# Penetrometer_V3_PCB.net
KiCad netlist of a schematic drawn in EAGLE
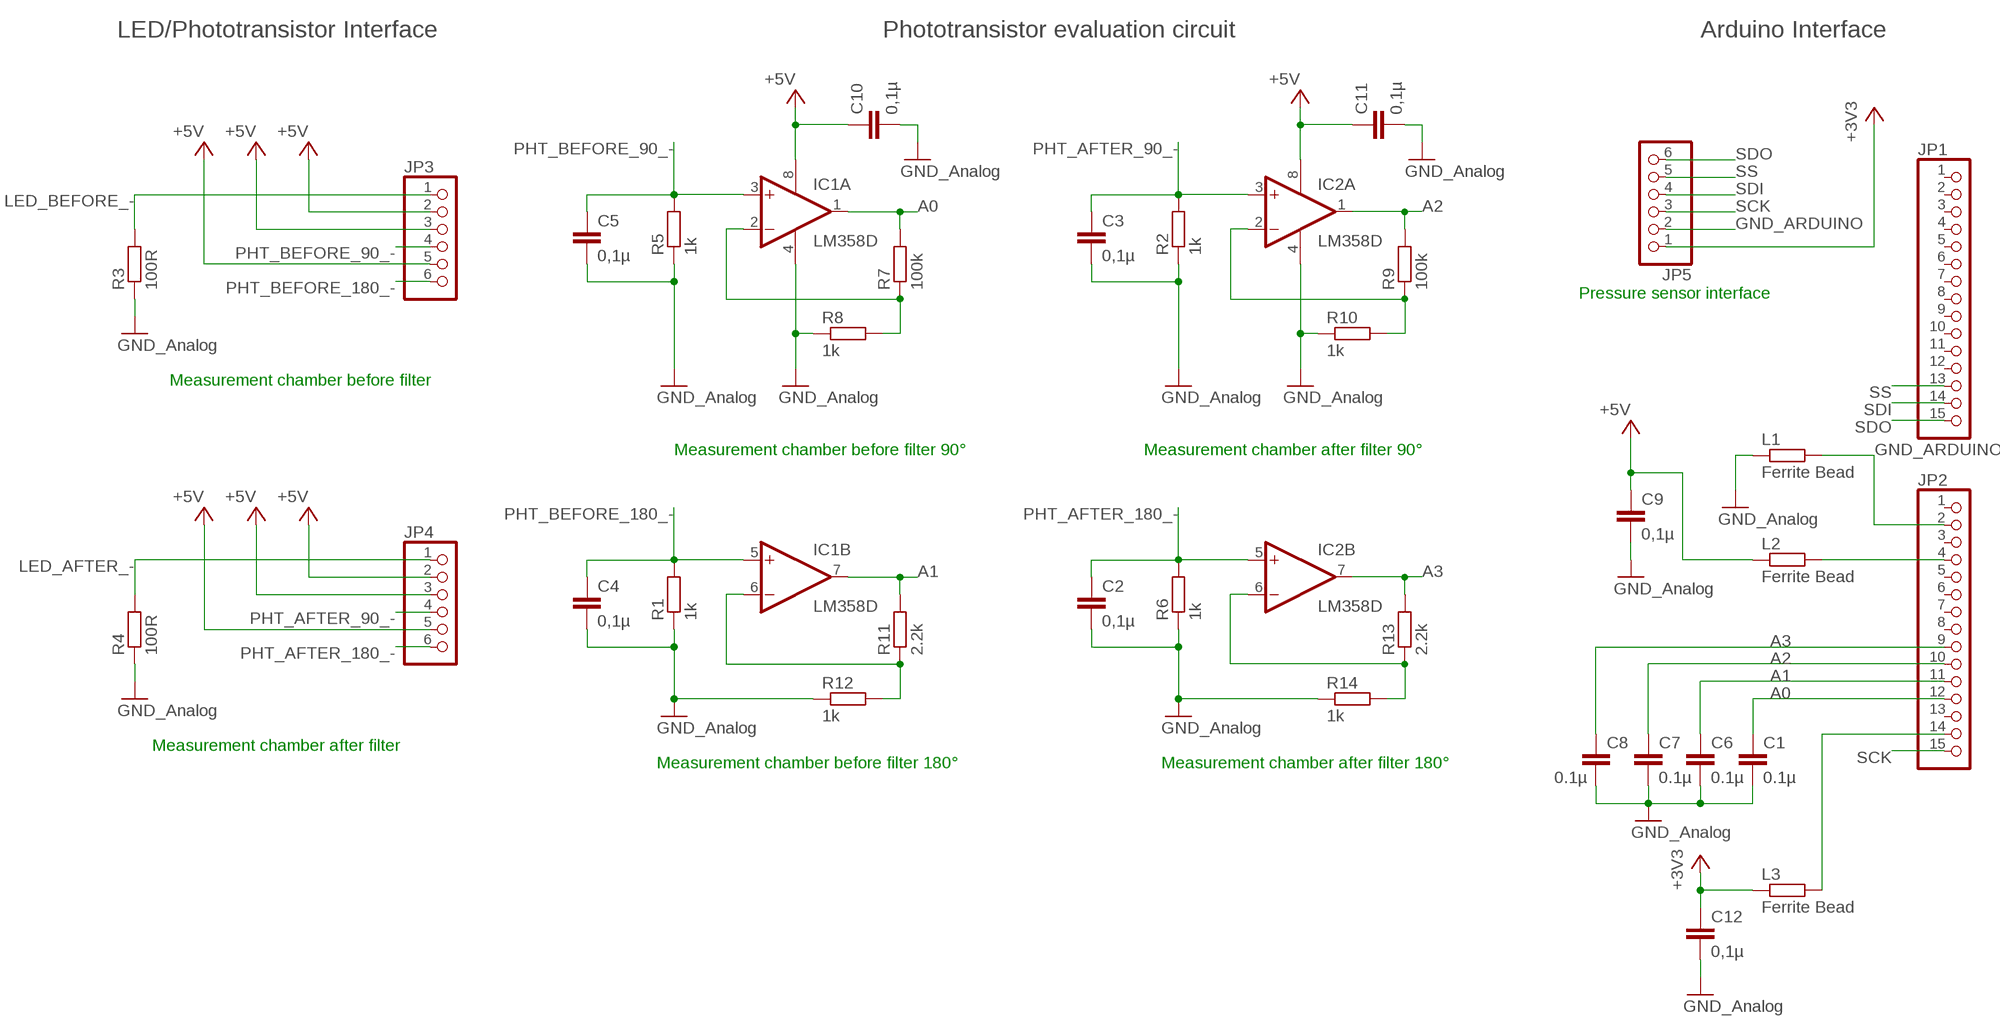
[diagram p0: schematic, sheet 1]

(export (version "E")
  (design (tool "Eeschema 10.0.6"))
  (components
    (comp (ref "C1")
      (value "0.1µ")
      (footprint "eagle-import:C0603K")
      (libsource (lib "eagle-import") (part "C-EUC0603K"))
    )
    (comp (ref "C2")
      (value "0,1µ")
      (footprint "eagle-import:C0603K")
      (libsource (lib "eagle-import") (part "C-EUC0603K"))
    )
    (comp (ref "C3")
      (value "0,1µ")
      (footprint "eagle-import:C0603K")
      (libsource (lib "eagle-import") (part "C-EUC0603K"))
    )
    (comp (ref "C4")
      (value "0,1µ")
      (footprint "eagle-import:C0603K")
      (libsource (lib "eagle-import") (part "C-EUC0603K"))
    )
    (comp (ref "C5")
      (value "0,1µ")
      (footprint "eagle-import:C0603K")
      (libsource (lib "eagle-import") (part "C-EUC0603K"))
    )
    (comp (ref "C6")
      (value "0.1µ")
      (footprint "eagle-import:C0603K")
      (libsource (lib "eagle-import") (part "C-EUC0603K"))
    )
    (comp (ref "C7")
      (value "0.1µ")
      (footprint "eagle-import:C0603K")
      (libsource (lib "eagle-import") (part "C-EUC0603K"))
    )
    (comp (ref "C8")
      (value "0.1µ")
      (footprint "eagle-import:C0603K")
      (libsource (lib "eagle-import") (part "C-EUC0603K"))
    )
    (comp (ref "C9")
      (value "0,1µ")
      (footprint "eagle-import:C0603K")
      (libsource (lib "eagle-import") (part "C-EUC0603K"))
    )
    (comp (ref "C10")
      (value "0,1µ")
      (footprint "eagle-import:C0603K")
      (libsource (lib "eagle-import") (part "C-EUC0603K"))
    )
    (comp (ref "C11")
      (value "0,1µ")
      (footprint "eagle-import:C0603K")
      (libsource (lib "eagle-import") (part "C-EUC0603K"))
    )
    (comp (ref "C12")
      (value "0,1µ")
      (footprint "eagle-import:C0603K")
      (libsource (lib "eagle-import") (part "C-EUC0603K"))
    )
    (comp (ref "IC1")
      (value "LM358D")
      (footprint "eagle-import:SO08")
      (libsource (lib "eagle-import") (part "LM358D"))
    )
    (comp (ref "IC2")
      (value "LM358D")
      (footprint "eagle-import:SO08")
      (libsource (lib "eagle-import") (part "LM358D"))
    )
    (comp (ref "JP1")
      (value "PINHD-1X15")
      (footprint "eagle-import:1X15")
      (libsource (lib "eagle-import") (part "PINHD-1X15"))
    )
    (comp (ref "JP2")
      (value "PINHD-1X15")
      (footprint "eagle-import:1X15")
      (libsource (lib "eagle-import") (part "PINHD-1X15"))
    )
    (comp (ref "JP3")
      (value "PINHD-1X6")
      (footprint "eagle-import:1X06")
      (libsource (lib "eagle-import") (part "PINHD-1X6"))
    )
    (comp (ref "JP4")
      (value "PINHD-1X6")
      (footprint "eagle-import:1X06")
      (libsource (lib "eagle-import") (part "PINHD-1X6"))
    )
    (comp (ref "JP5")
      (value "PINHD-1X6")
      (footprint "eagle-import:1X06")
      (libsource (lib "eagle-import") (part "PINHD-1X6"))
    )
    (comp (ref "L1")
      (value "Ferrite Bead")
      (footprint "eagle-import:R0603")
      (libsource (lib "eagle-import") (part "R-EU_R0603"))
    )
    (comp (ref "L2")
      (value "Ferrite Bead")
      (footprint "eagle-import:R0603")
      (libsource (lib "eagle-import") (part "R-EU_R0603"))
    )
    (comp (ref "L3")
      (value "Ferrite Bead")
      (footprint "eagle-import:R0603")
      (libsource (lib "eagle-import") (part "R-EU_R0603"))
    )
    (comp (ref "R1")
      (value "1k")
      (footprint "eagle-import:R0603")
      (libsource (lib "eagle-import") (part "R-EU_R0603"))
    )
    (comp (ref "R2")
      (value "1k")
      (footprint "eagle-import:R0603")
      (libsource (lib "eagle-import") (part "R-EU_R0603"))
    )
    (comp (ref "R3")
      (value "100R")
      (footprint "eagle-import:R0603")
      (libsource (lib "eagle-import") (part "R-EU_R0603"))
    )
    (comp (ref "R4")
      (value "100R")
      (footprint "eagle-import:R0603")
      (libsource (lib "eagle-import") (part "R-EU_R0603"))
    )
    (comp (ref "R5")
      (value "1k")
      (footprint "eagle-import:R0603")
      (libsource (lib "eagle-import") (part "R-EU_R0603"))
    )
    (comp (ref "R6")
      (value "1k")
      (footprint "eagle-import:R0603")
      (libsource (lib "eagle-import") (part "R-EU_R0603"))
    )
    (comp (ref "R7")
      (value "100k")
      (footprint "eagle-import:R0603")
      (libsource (lib "eagle-import") (part "R-EU_R0603"))
    )
    (comp (ref "R8")
      (value "1k")
      (footprint "eagle-import:R0603")
      (libsource (lib "eagle-import") (part "R-EU_R0603"))
    )
    (comp (ref "R9")
      (value "100k")
      (footprint "eagle-import:R0603")
      (libsource (lib "eagle-import") (part "R-EU_R0603"))
    )
    (comp (ref "R10")
      (value "1k")
      (footprint "eagle-import:R0603")
      (libsource (lib "eagle-import") (part "R-EU_R0603"))
    )
    (comp (ref "R11")
      (value "2.2k")
      (footprint "eagle-import:R0603")
      (libsource (lib "eagle-import") (part "R-EU_R0603"))
    )
    (comp (ref "R12")
      (value "1k")
      (footprint "eagle-import:R0603")
      (libsource (lib "eagle-import") (part "R-EU_R0603"))
    )
    (comp (ref "R13")
      (value "2.2k")
      (footprint "eagle-import:R0603")
      (libsource (lib "eagle-import") (part "R-EU_R0603"))
    )
    (comp (ref "R14")
      (value "1k")
      (footprint "eagle-import:R0603")
      (libsource (lib "eagle-import") (part "R-EU_R0603"))
    )
  )
  (nets
    (net (code "1") (name "+3V3") (class "Default")
      (node (ref "C12") (pin "1") (pinfunction "1_1") (pintype "passive"))
      (node (ref "JP5") (pin "1") (pinfunction "1_1") (pintype "passive"))
      (node (ref "L3") (pin "1") (pinfunction "1_1") (pintype "passive"))
    )
    (net (code "2") (name "+5V") (class "Default")
      (node (ref "C10") (pin "1") (pinfunction "1_1") (pintype "passive"))
      (node (ref "C11") (pin "1") (pinfunction "1_1") (pintype "passive"))
      (node (ref "C9") (pin "1") (pinfunction "1_1") (pintype "passive"))
      (node (ref "IC1") (pin "8") (pinfunction "V+_8") (pintype "power_in"))
      (node (ref "IC2") (pin "8") (pinfunction "V+_8") (pintype "power_in"))
      (node (ref "JP3") (pin "2") (pinfunction "2_2") (pintype "passive"))
      (node (ref "JP3") (pin "3") (pinfunction "3_3") (pintype "passive"))
      (node (ref "JP3") (pin "5") (pinfunction "5_5") (pintype "passive"))
      (node (ref "JP4") (pin "2") (pinfunction "2_2") (pintype "passive"))
      (node (ref "JP4") (pin "3") (pinfunction "3_3") (pintype "passive"))
      (node (ref "JP4") (pin "5") (pinfunction "5_5") (pintype "passive"))
      (node (ref "L2") (pin "1") (pinfunction "1_1") (pintype "passive"))
    )
    (net (code "3") (name "/A0") (class "Default")
      (node (ref "C1") (pin "1") (pinfunction "1_1") (pintype "passive"))
      (node (ref "IC1") (pin "1") (pinfunction "OUT_1") (pintype "output"))
      (node (ref "JP2") (pin "12") (pinfunction "12_12") (pintype "passive"))
      (node (ref "R7") (pin "2") (pinfunction "2_2") (pintype "passive"))
    )
    (net (code "4") (name "/A1") (class "Default")
      (node (ref "C6") (pin "1") (pinfunction "1_1") (pintype "passive"))
      (node (ref "IC1") (pin "7") (pinfunction "OUT_7") (pintype "output"))
      (node (ref "JP2") (pin "11") (pinfunction "11_11") (pintype "passive"))
      (node (ref "R11") (pin "2") (pinfunction "2_2") (pintype "passive"))
    )
    (net (code "5") (name "/A2") (class "Default")
      (node (ref "C7") (pin "1") (pinfunction "1_1") (pintype "passive"))
      (node (ref "IC2") (pin "1") (pinfunction "OUT_1") (pintype "output"))
      (node (ref "JP2") (pin "10") (pinfunction "10_10") (pintype "passive"))
      (node (ref "R9") (pin "2") (pinfunction "2_2") (pintype "passive"))
    )
    (net (code "6") (name "/A3") (class "Default")
      (node (ref "C8") (pin "1") (pinfunction "1_1") (pintype "passive"))
      (node (ref "IC2") (pin "7") (pinfunction "OUT_7") (pintype "output"))
      (node (ref "JP2") (pin "9") (pinfunction "9_9") (pintype "passive"))
      (node (ref "R13") (pin "2") (pinfunction "2_2") (pintype "passive"))
    )
    (net (code "7") (name "/GND_ARDUINO") (class "Default")
      (node (ref "JP2") (pin "2") (pinfunction "2_2") (pintype "passive"))
      (node (ref "JP5") (pin "2") (pinfunction "2_2") (pintype "passive"))
      (node (ref "L1") (pin "2") (pinfunction "2_2") (pintype "passive"))
    )
    (net (code "8") (name "/LED_AFTER_-") (class "Default")
      (node (ref "JP4") (pin "1") (pinfunction "1_1") (pintype "passive"))
      (node (ref "R4") (pin "2") (pinfunction "2_2") (pintype "passive"))
    )
    (net (code "9") (name "/LED_BEFORE_-") (class "Default")
      (node (ref "JP3") (pin "1") (pinfunction "1_1") (pintype "passive"))
      (node (ref "R3") (pin "2") (pinfunction "2_2") (pintype "passive"))
    )
    (net (code "10") (name "/PHT_AFTER_90_-") (class "Default")
      (node (ref "C3") (pin "1") (pinfunction "1_1") (pintype "passive"))
      (node (ref "IC2") (pin "3") (pinfunction "+IN_3") (pintype "input"))
      (node (ref "JP4") (pin "4") (pinfunction "4_4") (pintype "passive"))
      (node (ref "R2") (pin "2") (pinfunction "2_2") (pintype "passive"))
    )
    (net (code "11") (name "/PHT_AFTER_180_-") (class "Default")
      (node (ref "C2") (pin "1") (pinfunction "1_1") (pintype "passive"))
      (node (ref "IC2") (pin "5") (pinfunction "+IN_5") (pintype "input"))
      (node (ref "JP4") (pin "6") (pinfunction "6_6") (pintype "passive"))
      (node (ref "R6") (pin "2") (pinfunction "2_2") (pintype "passive"))
    )
    (net (code "12") (name "/PHT_BEFORE_90_-") (class "Default")
      (node (ref "C5") (pin "1") (pinfunction "1_1") (pintype "passive"))
      (node (ref "IC1") (pin "3") (pinfunction "+IN_3") (pintype "input"))
      (node (ref "JP3") (pin "4") (pinfunction "4_4") (pintype "passive"))
      (node (ref "R5") (pin "2") (pinfunction "2_2") (pintype "passive"))
    )
    (net (code "13") (name "/PHT_BEFORE_180_-") (class "Default")
      (node (ref "C4") (pin "1") (pinfunction "1_1") (pintype "passive"))
      (node (ref "IC1") (pin "5") (pinfunction "+IN_5") (pintype "input"))
      (node (ref "JP3") (pin "6") (pinfunction "6_6") (pintype "passive"))
      (node (ref "R1") (pin "2") (pinfunction "2_2") (pintype "passive"))
    )
    (net (code "14") (name "/SCK") (class "Default")
      (node (ref "JP2") (pin "15") (pinfunction "15_15") (pintype "passive"))
      (node (ref "JP5") (pin "3") (pinfunction "3_3") (pintype "passive"))
    )
    (net (code "15") (name "/SDI") (class "Default")
      (node (ref "JP1") (pin "14") (pinfunction "14_14") (pintype "passive"))
      (node (ref "JP5") (pin "4") (pinfunction "4_4") (pintype "passive"))
    )
    (net (code "16") (name "/SDO") (class "Default")
      (node (ref "JP1") (pin "15") (pinfunction "15_15") (pintype "passive"))
      (node (ref "JP5") (pin "6") (pinfunction "6_6") (pintype "passive"))
    )
    (net (code "17") (name "/SS") (class "Default")
      (node (ref "JP1") (pin "13") (pinfunction "13_13") (pintype "passive"))
      (node (ref "JP5") (pin "5") (pinfunction "5_5") (pintype "passive"))
    )
    (net (code "18") (name "GND_Analog") (class "Default")
      (node (ref "C1") (pin "2") (pinfunction "2_2") (pintype "passive"))
      (node (ref "C10") (pin "2") (pinfunction "2_2") (pintype "passive"))
      (node (ref "C11") (pin "2") (pinfunction "2_2") (pintype "passive"))
      (node (ref "C12") (pin "2") (pinfunction "2_2") (pintype "passive"))
      (node (ref "C2") (pin "2") (pinfunction "2_2") (pintype "passive"))
      (node (ref "C3") (pin "2") (pinfunction "2_2") (pintype "passive"))
      (node (ref "C4") (pin "2") (pinfunction "2_2") (pintype "passive"))
      (node (ref "C5") (pin "2") (pinfunction "2_2") (pintype "passive"))
      (node (ref "C6") (pin "2") (pinfunction "2_2") (pintype "passive"))
      (node (ref "C7") (pin "2") (pinfunction "2_2") (pintype "passive"))
      (node (ref "C8") (pin "2") (pinfunction "2_2") (pintype "passive"))
      (node (ref "C9") (pin "2") (pinfunction "2_2") (pintype "passive"))
      (node (ref "IC1") (pin "4") (pinfunction "V-_4") (pintype "power_in"))
      (node (ref "IC2") (pin "4") (pinfunction "V-_4") (pintype "power_in"))
      (node (ref "L1") (pin "1") (pinfunction "1_1") (pintype "passive"))
      (node (ref "R1") (pin "1") (pinfunction "1_1") (pintype "passive"))
      (node (ref "R10") (pin "1") (pinfunction "1_1") (pintype "passive"))
      (node (ref "R12") (pin "1") (pinfunction "1_1") (pintype "passive"))
      (node (ref "R14") (pin "1") (pinfunction "1_1") (pintype "passive"))
      (node (ref "R2") (pin "1") (pinfunction "1_1") (pintype "passive"))
      (node (ref "R3") (pin "1") (pinfunction "1_1") (pintype "passive"))
      (node (ref "R4") (pin "1") (pinfunction "1_1") (pintype "passive"))
      (node (ref "R5") (pin "1") (pinfunction "1_1") (pintype "passive"))
      (node (ref "R6") (pin "1") (pinfunction "1_1") (pintype "passive"))
      (node (ref "R8") (pin "1") (pinfunction "1_1") (pintype "passive"))
    )
    (net (code "19") (name "Net-(IC1A--IN)") (class "Default")
      (node (ref "IC1") (pin "2") (pinfunction "-IN_2") (pintype "input"))
      (node (ref "R7") (pin "1") (pinfunction "1_1") (pintype "passive"))
      (node (ref "R8") (pin "2") (pinfunction "2_2") (pintype "passive"))
    )
    (net (code "20") (name "Net-(IC1B--IN)") (class "Default")
      (node (ref "IC1") (pin "6") (pinfunction "-IN_6") (pintype "input"))
      (node (ref "R11") (pin "1") (pinfunction "1_1") (pintype "passive"))
      (node (ref "R12") (pin "2") (pinfunction "2_2") (pintype "passive"))
    )
    (net (code "21") (name "Net-(IC2A--IN)") (class "Default")
      (node (ref "IC2") (pin "2") (pinfunction "-IN_2") (pintype "input"))
      (node (ref "R10") (pin "2") (pinfunction "2_2") (pintype "passive"))
      (node (ref "R9") (pin "1") (pinfunction "1_1") (pintype "passive"))
    )
    (net (code "22") (name "Net-(IC2B--IN)") (class "Default")
      (node (ref "IC2") (pin "6") (pinfunction "-IN_6") (pintype "input"))
      (node (ref "R13") (pin "1") (pinfunction "1_1") (pintype "passive"))
      (node (ref "R14") (pin "2") (pinfunction "2_2") (pintype "passive"))
    )
    (net (code "23") (name "Net-(JP2-Pad4)") (class "Default")
      (node (ref "JP2") (pin "4") (pinfunction "4_4") (pintype "passive"))
      (node (ref "L2") (pin "2") (pinfunction "2_2") (pintype "passive"))
    )
    (net (code "24") (name "Net-(JP2-Pad14)") (class "Default")
      (node (ref "JP2") (pin "14") (pinfunction "14_14") (pintype "passive"))
      (node (ref "L3") (pin "2") (pinfunction "2_2") (pintype "passive"))
    )
    (net (code "25") (name "unconnected-(JP1-Pad1)") (class "Default")
      (node (ref "JP1") (pin "1") (pinfunction "1_1") (pintype "passive"))
    )
    (net (code "26") (name "unconnected-(JP1-Pad2)") (class "Default")
      (node (ref "JP1") (pin "2") (pinfunction "2_2") (pintype "passive"))
    )
    (net (code "27") (name "unconnected-(JP1-Pad3)") (class "Default")
      (node (ref "JP1") (pin "3") (pinfunction "3_3") (pintype "passive"))
    )
    (net (code "28") (name "unconnected-(JP1-Pad4)") (class "Default")
      (node (ref "JP1") (pin "4") (pinfunction "4_4") (pintype "passive"))
    )
    (net (code "29") (name "unconnected-(JP1-Pad5)") (class "Default")
      (node (ref "JP1") (pin "5") (pinfunction "5_5") (pintype "passive"))
    )
    (net (code "30") (name "unconnected-(JP1-Pad6)") (class "Default")
      (node (ref "JP1") (pin "6") (pinfunction "6_6") (pintype "passive"))
    )
    (net (code "31") (name "unconnected-(JP1-Pad7)") (class "Default")
      (node (ref "JP1") (pin "7") (pinfunction "7_7") (pintype "passive"))
    )
    (net (code "32") (name "unconnected-(JP1-Pad8)") (class "Default")
      (node (ref "JP1") (pin "8") (pinfunction "8_8") (pintype "passive"))
    )
    (net (code "33") (name "unconnected-(JP1-Pad9)") (class "Default")
      (node (ref "JP1") (pin "9") (pinfunction "9_9") (pintype "passive"))
    )
    (net (code "34") (name "unconnected-(JP1-Pad10)") (class "Default")
      (node (ref "JP1") (pin "10") (pinfunction "10_10") (pintype "passive"))
    )
    (net (code "35") (name "unconnected-(JP1-Pad11)") (class "Default")
      (node (ref "JP1") (pin "11") (pinfunction "11_11") (pintype "passive"))
    )
    (net (code "36") (name "unconnected-(JP1-Pad12)") (class "Default")
      (node (ref "JP1") (pin "12") (pinfunction "12_12") (pintype "passive"))
    )
    (net (code "37") (name "unconnected-(JP2-Pad1)") (class "Default")
      (node (ref "JP2") (pin "1") (pinfunction "1_1") (pintype "passive"))
    )
    (net (code "38") (name "unconnected-(JP2-Pad3)") (class "Default")
      (node (ref "JP2") (pin "3") (pinfunction "3_3") (pintype "passive"))
    )
    (net (code "39") (name "unconnected-(JP2-Pad5)") (class "Default")
      (node (ref "JP2") (pin "5") (pinfunction "5_5") (pintype "passive"))
    )
    (net (code "40") (name "unconnected-(JP2-Pad6)") (class "Default")
      (node (ref "JP2") (pin "6") (pinfunction "6_6") (pintype "passive"))
    )
    (net (code "41") (name "unconnected-(JP2-Pad7)") (class "Default")
      (node (ref "JP2") (pin "7") (pinfunction "7_7") (pintype "passive"))
    )
    (net (code "42") (name "unconnected-(JP2-Pad8)") (class "Default")
      (node (ref "JP2") (pin "8") (pinfunction "8_8") (pintype "passive"))
    )
    (net (code "43") (name "unconnected-(JP2-Pad13)") (class "Default")
      (node (ref "JP2") (pin "13") (pinfunction "13_13") (pintype "passive"))
    )
  )
)
